# Control.net
KiCad netlist of a schematic drawn in Altium Designer
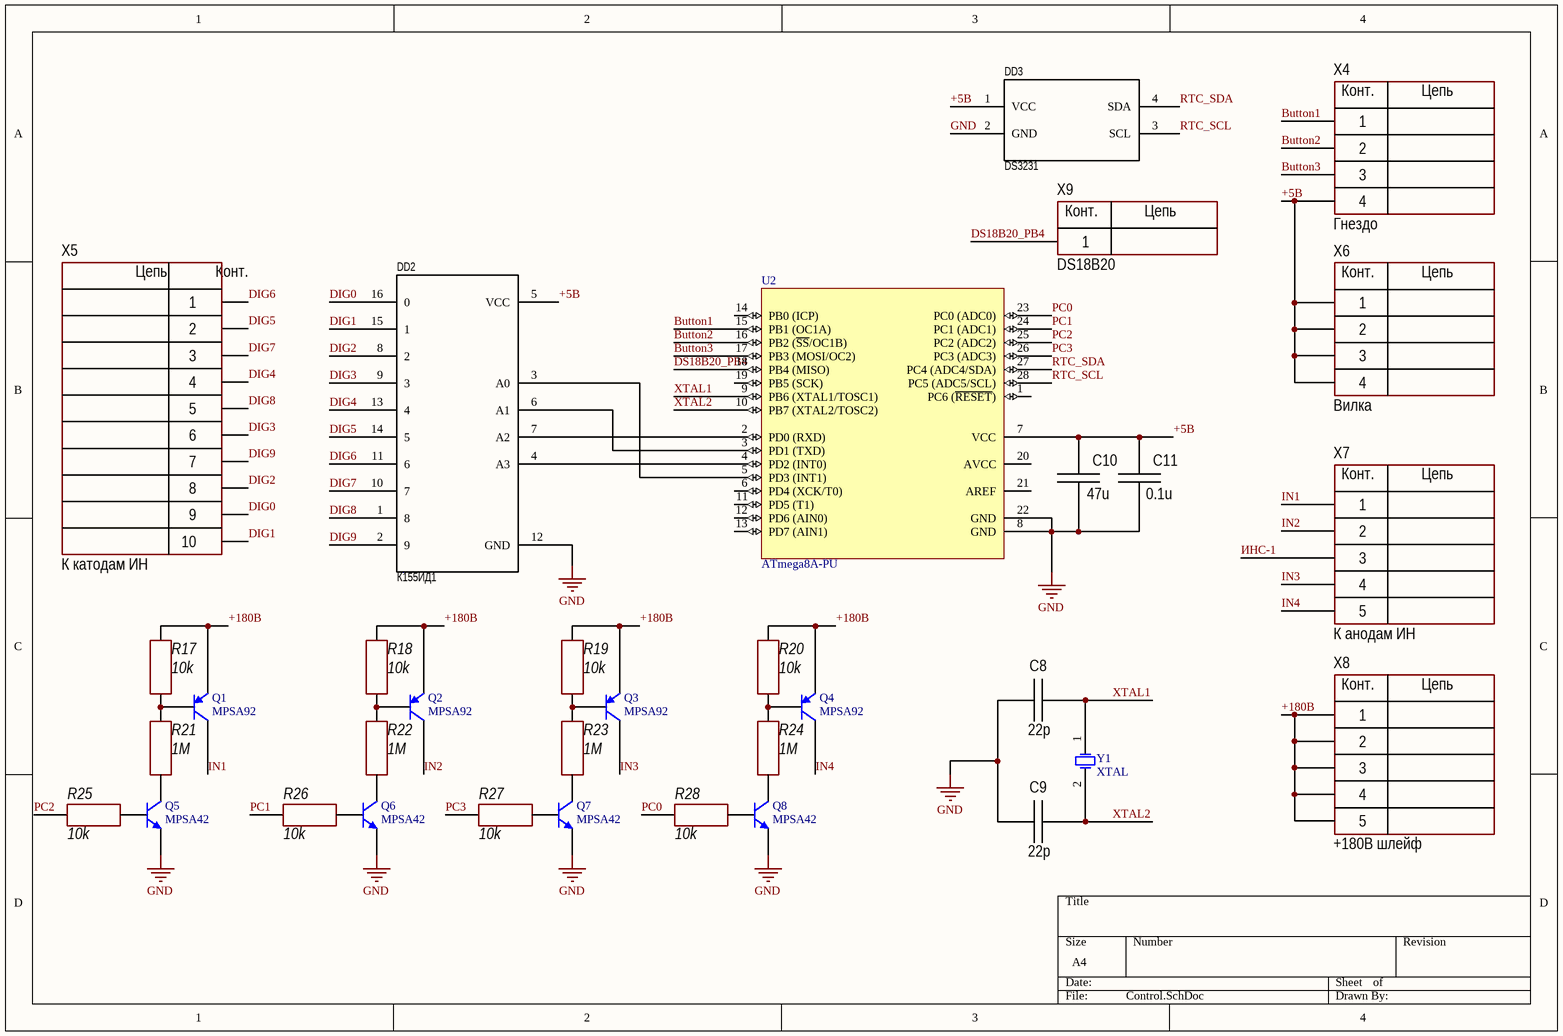
[diagram p0: Control.SchDoc]

(export (version "E")
  (design (tool "Eeschema 10.0.6"))
  (components
    (comp (ref "C8") (value "22p") (footprint "CAP: DEBB33D") (libsource (lib "Discrete") (part "Capacitor")))
    (comp (ref "C9") (value "22p") (footprint "CAP: DEBB33D") (libsource (lib "Discrete") (part "Capacitor")))
    (comp (ref "C10")
      (value "47u")
      (footprint "CAP: DEBB33D")
      (libsource (lib "Discrete") (part "Capacitor"))
    )
    (comp (ref "C11")
      (value "0.1u")
      (footprint "CAP: DEBB33D")
      (libsource (lib "Discrete") (part "Capacitor"))
    )
    (comp (ref "DD2") (value "К155ИД1") (footprint "DIP16") (libsource (lib "K155ID1") (part "K155ID1")))
    (comp (ref "DD3") (value "DS3231") (footprint "DS3231") (libsource (lib "DS3231") (part "DS3231")))
    (comp (ref "Q1")
      (value "MPSA92")
      (footprint "TO-92A")
      (description "PNP General Purpose Amplifier")
      (fields (field (name "PUBLISHER") "Altium Limited"))
      (libsource (lib "Miscellaneous Devices") (part "2N3906"))
    )
    (comp (ref "Q2")
      (value "MPSA92")
      (footprint "TO-92A")
      (description "PNP General Purpose Amplifier")
      (fields (field (name "PUBLISHER") "Altium Limited"))
      (libsource (lib "Miscellaneous Devices") (part "2N3906"))
    )
    (comp (ref "Q3")
      (value "MPSA92")
      (footprint "TO-92A")
      (description "PNP General Purpose Amplifier")
      (fields (field (name "PUBLISHER") "Altium Limited"))
      (libsource (lib "Miscellaneous Devices") (part "2N3906"))
    )
    (comp (ref "Q4")
      (value "MPSA92")
      (footprint "TO-92A")
      (description "PNP General Purpose Amplifier")
      (fields (field (name "PUBLISHER") "Altium Limited"))
      (libsource (lib "Miscellaneous Devices") (part "2N3906"))
    )
    (comp (ref "Q5")
      (value "MPSA42")
      (footprint "TO-92A")
      (description "NPN General Purpose Amplifier")
      (fields (field (name "PUBLISHER") "Altium Limited"))
      (libsource (lib "Miscellaneous Devices") (part "2N3904"))
    )
    (comp (ref "Q6")
      (value "MPSA42")
      (footprint "TO-92A")
      (description "NPN General Purpose Amplifier")
      (fields (field (name "PUBLISHER") "Altium Limited"))
      (libsource (lib "Miscellaneous Devices") (part "2N3904"))
    )
    (comp (ref "Q7")
      (value "MPSA42")
      (footprint "TO-92A")
      (description "NPN General Purpose Amplifier")
      (fields (field (name "PUBLISHER") "Altium Limited"))
      (libsource (lib "Miscellaneous Devices") (part "2N3904"))
    )
    (comp (ref "Q8")
      (value "MPSA42")
      (footprint "TO-92A")
      (description "NPN General Purpose Amplifier")
      (fields (field (name "PUBLISHER") "Altium Limited"))
      (libsource (lib "Miscellaneous Devices") (part "2N3904"))
    )
    (comp (ref "R17")
      (value "10k")
      (footprint "MLT")
      (description "MLT")
      (libsource (lib "") (part "Resistor_1"))
    )
    (comp (ref "R18")
      (value "10k")
      (footprint "MLT")
      (description "MLT")
      (libsource (lib "") (part "Resistor_1"))
    )
    (comp (ref "R19")
      (value "10k")
      (footprint "MLT")
      (description "MLT")
      (libsource (lib "") (part "Resistor_1"))
    )
    (comp (ref "R20")
      (value "10k")
      (footprint "MLT")
      (description "MLT")
      (libsource (lib "") (part "Resistor_1"))
    )
    (comp (ref "R21")
      (value "1M")
      (footprint "MLT")
      (description "MLT")
      (libsource (lib "") (part "Resistor_1"))
    )
    (comp (ref "R22")
      (value "1M")
      (footprint "MLT")
      (description "MLT")
      (libsource (lib "") (part "Resistor_1"))
    )
    (comp (ref "R23")
      (value "1M")
      (footprint "MLT")
      (description "MLT")
      (libsource (lib "") (part "Resistor_1"))
    )
    (comp (ref "R24")
      (value "1M")
      (footprint "MLT")
      (description "MLT")
      (libsource (lib "") (part "Resistor_1"))
    )
    (comp (ref "R25")
      (value "10k")
      (footprint "MLT")
      (description "MLT")
      (libsource (lib "Resistor_MLT") (part "Resistor"))
    )
    (comp (ref "R26")
      (value "10k")
      (footprint "MLT")
      (description "MLT")
      (libsource (lib "Resistor_MLT") (part "Resistor"))
    )
    (comp (ref "R27")
      (value "10k")
      (footprint "MLT")
      (description "MLT")
      (libsource (lib "Resistor_MLT") (part "Resistor"))
    )
    (comp (ref "R28")
      (value "10k")
      (footprint "MLT")
      (description "MLT")
      (libsource (lib "Resistor_MLT") (part "Resistor"))
    )
    (comp (ref "U2")
      (value "ATmega8A-PU")
      (footprint "28P3")
      (fields (field (name "PUBLISHER") "Altium Limited"))
      (libsource (lib "Atmel Microcontroller 8-Bit megaAVR") (part "ATmega8A-PU"))
    )
    (comp (ref "X4")
      (value "Гнездо")
      (footprint "CON: PBS-4")
      (libsource (lib "Connectors") (part "4-Connector"))
    )
    (comp (ref "X5")
      (value "К катодам ИН")
      (footprint "CON: PBS-10")
      (libsource (lib "Connectors") (part "10-Connector"))
    )
    (comp (ref "X6")
      (value "Вилка")
      (footprint "CON: PLS-4")
      (libsource (lib "Connectors") (part "4-Connector"))
    )
    (comp (ref "X7")
      (value "К анодам ИН")
      (footprint "CON: PBS-5")
      (libsource (lib "Connectors") (part "5-Connector"))
    )
    (comp (ref "X8")
      (value "+180В шлейф")
      (footprint "CON: PBS-5")
      (libsource (lib "Connectors") (part "5-Connector"))
    )
    (comp (ref "X9")
      (value "DS18B20")
      (footprint "CON: PADS 1x1mm")
      (libsource (lib "Connectors") (part "1-Connector"))
    )
    (comp (ref "Y1")
      (value "XTAL")
      (footprint "R38")
      (description "Crystal Oscillator")
      (fields (field (name "PUBLISHER") "Altium Limited"))
      (libsource (lib "Miscellaneous Devices") (part "XTAL"))
    )
  )
  (nets
    (net (code "1") (name "/+5В") (class "Default")
      (node (ref "C10") (pin "1") (pinfunction "1_1") (pintype "power_in"))
      (node (ref "C11") (pin "1") (pinfunction "1_1") (pintype "power_in"))
      (node (ref "DD2") (pin "5") (pinfunction "VCC_5") (pintype "passive"))
      (node (ref "DD3") (pin "1") (pinfunction "VCC_1") (pintype "passive"))
      (node (ref "U2") (pin "7") (pinfunction "VCC_7") (pintype "power_in"))
      (node (ref "X4") (pin "4") (pinfunction "4_4") (pintype "power_in"))
      (node (ref "X6") (pin "1") (pinfunction "1_1") (pintype "passive"))
      (node (ref "X6") (pin "2") (pinfunction "2_2") (pintype "passive"))
      (node (ref "X6") (pin "3") (pinfunction "3_3") (pintype "power_in"))
      (node (ref "X6") (pin "4") (pinfunction "4_4") (pintype "power_in"))
    )
    (net (code "2") (name "/+180В") (class "Default")
      (node (ref "Q1") (pin "1") (pinfunction "E_1") (pintype "passive"))
      (node (ref "Q2") (pin "1") (pinfunction "E_1") (pintype "passive"))
      (node (ref "Q3") (pin "1") (pinfunction "E_1") (pintype "passive"))
      (node (ref "Q4") (pin "1") (pinfunction "E_1") (pintype "passive"))
      (node (ref "R17") (pin "2") (pintype "passive"))
      (node (ref "R18") (pin "2") (pintype "passive"))
      (node (ref "R19") (pin "2") (pintype "passive"))
      (node (ref "R20") (pin "2") (pintype "passive"))
      (node (ref "X8") (pin "1") (pinfunction "1_1") (pintype "passive"))
      (node (ref "X8") (pin "2") (pinfunction "2_2") (pintype "passive"))
      (node (ref "X8") (pin "3") (pinfunction "3_3") (pintype "power_in"))
      (node (ref "X8") (pin "4") (pinfunction "4_4") (pintype "power_in"))
      (node (ref "X8") (pin "5") (pinfunction "5_5") (pintype "power_in"))
    )
    (net (code "3") (name "/Button1") (class "Default")
      (node (ref "U2") (pin "15") (pinfunction "PB1_(OC1A)_15") (pintype "bidirectional"))
      (node (ref "X4") (pin "1") (pinfunction "1_1") (pintype "passive"))
    )
    (net (code "4") (name "/Button2") (class "Default")
      (node (ref "U2") (pin "16") (pinfunction "PB2_(~{SS}/OC1B)_16") (pintype "bidirectional"))
      (node (ref "X4") (pin "2") (pinfunction "2_2") (pintype "passive"))
    )
    (net (code "5") (name "/Button3") (class "Default")
      (node (ref "U2") (pin "17") (pinfunction "PB3_(MOSI/OC2)_17") (pintype "bidirectional"))
      (node (ref "X4") (pin "3") (pinfunction "3_3") (pintype "power_in"))
    )
    (net (code "6") (name "/DIG0") (class "Default")
      (node (ref "DD2") (pin "16") (pinfunction "0_16") (pintype "passive"))
      (node (ref "X5") (pin "9") (pinfunction "9_9") (pintype "power_in"))
    )
    (net (code "7") (name "/DIG1") (class "Default")
      (node (ref "DD2") (pin "15") (pinfunction "1_15") (pintype "passive"))
      (node (ref "X5") (pin "10") (pinfunction "10_10") (pintype "power_in"))
    )
    (net (code "8") (name "/DIG2") (class "Default")
      (node (ref "DD2") (pin "8") (pinfunction "2_8") (pintype "passive"))
      (node (ref "X5") (pin "8") (pinfunction "8_8") (pintype "power_in"))
    )
    (net (code "9") (name "/DIG3") (class "Default")
      (node (ref "DD2") (pin "9") (pinfunction "3_9") (pintype "passive"))
      (node (ref "X5") (pin "6") (pinfunction "6_6") (pintype "power_in"))
    )
    (net (code "10") (name "/DIG4") (class "Default")
      (node (ref "DD2") (pin "13") (pinfunction "4_13") (pintype "passive"))
      (node (ref "X5") (pin "4") (pinfunction "4_4") (pintype "power_in"))
    )
    (net (code "11") (name "/DIG5") (class "Default")
      (node (ref "DD2") (pin "14") (pinfunction "5_14") (pintype "passive"))
      (node (ref "X5") (pin "2") (pinfunction "2_2") (pintype "passive"))
    )
    (net (code "12") (name "/DIG6") (class "Default")
      (node (ref "DD2") (pin "11") (pinfunction "6_11") (pintype "passive"))
      (node (ref "X5") (pin "1") (pinfunction "1_1") (pintype "passive"))
    )
    (net (code "13") (name "/DIG7") (class "Default")
      (node (ref "DD2") (pin "10") (pinfunction "7_10") (pintype "passive"))
      (node (ref "X5") (pin "3") (pinfunction "3_3") (pintype "power_in"))
    )
    (net (code "14") (name "/DIG8") (class "Default")
      (node (ref "DD2") (pin "1") (pinfunction "8_1") (pintype "passive"))
      (node (ref "X5") (pin "5") (pinfunction "5_5") (pintype "power_in"))
    )
    (net (code "15") (name "/DIG9") (class "Default")
      (node (ref "DD2") (pin "2") (pinfunction "9_2") (pintype "passive"))
      (node (ref "X5") (pin "7") (pinfunction "7_7") (pintype "power_in"))
    )
    (net (code "16") (name "/DS18B20_PB4") (class "Default")
      (node (ref "U2") (pin "18") (pinfunction "PB4_(MISO)_18") (pintype "bidirectional"))
      (node (ref "X9") (pin "1") (pinfunction "1_1") (pintype "passive"))
    )
    (net (code "17") (name "/IN1") (class "Default")
      (node (ref "Q1") (pin "3") (pinfunction "C_3") (pintype "passive"))
      (node (ref "X7") (pin "1") (pinfunction "1_1") (pintype "passive"))
    )
    (net (code "18") (name "/IN2") (class "Default")
      (node (ref "Q2") (pin "3") (pinfunction "C_3") (pintype "passive"))
      (node (ref "X7") (pin "2") (pinfunction "2_2") (pintype "passive"))
    )
    (net (code "19") (name "/IN3") (class "Default")
      (node (ref "Q3") (pin "3") (pinfunction "C_3") (pintype "passive"))
      (node (ref "X7") (pin "4") (pinfunction "4_4") (pintype "power_in"))
    )
    (net (code "20") (name "/IN4") (class "Default")
      (node (ref "Q4") (pin "3") (pinfunction "C_3") (pintype "passive"))
      (node (ref "X7") (pin "5") (pinfunction "5_5") (pintype "power_in"))
    )
    (net (code "21") (name "/PC0") (class "Default")
      (node (ref "R28") (pin "2") (pintype "passive"))
      (node (ref "U2") (pin "23") (pinfunction "PC0_(ADC0)_23") (pintype "bidirectional"))
    )
    (net (code "22") (name "/PC1") (class "Default")
      (node (ref "R26") (pin "2") (pintype "passive"))
      (node (ref "U2") (pin "24") (pinfunction "PC1_(ADC1)_24") (pintype "bidirectional"))
    )
    (net (code "23") (name "/PC2") (class "Default")
      (node (ref "R25") (pin "2") (pintype "passive"))
      (node (ref "U2") (pin "25") (pinfunction "PC2_(ADC2)_25") (pintype "bidirectional"))
    )
    (net (code "24") (name "/PC3") (class "Default")
      (node (ref "R27") (pin "2") (pintype "passive"))
      (node (ref "U2") (pin "26") (pinfunction "PC3_(ADC3)_26") (pintype "bidirectional"))
    )
    (net (code "25") (name "/RTC_SCL") (class "Default")
      (node (ref "DD3") (pin "3") (pinfunction "SCL_3") (pintype "passive"))
      (node (ref "U2") (pin "28") (pinfunction "PC5_(ADC5/SCL)_28") (pintype "bidirectional"))
    )
    (net (code "26") (name "/RTC_SDA") (class "Default")
      (node (ref "DD3") (pin "4") (pinfunction "SDA_4") (pintype "passive"))
      (node (ref "U2") (pin "27") (pinfunction "PC4_(ADC4/SDA)_27") (pintype "bidirectional"))
    )
    (net (code "27") (name "/XTAL1") (class "Default")
      (node (ref "C8") (pin "2") (pinfunction "2_2") (pintype "power_in"))
      (node (ref "U2") (pin "9") (pinfunction "PB6_(XTAL1/TOSC1)_9") (pintype "bidirectional"))
      (node (ref "Y1") (pin "1") (pinfunction "OSC1_1") (pintype "passive"))
    )
    (net (code "28") (name "/XTAL2") (class "Default")
      (node (ref "C9") (pin "2") (pinfunction "2_2") (pintype "power_in"))
      (node (ref "U2") (pin "10") (pinfunction "PB7_(XTAL2/TOSC2)_10") (pintype "bidirectional"))
      (node (ref "Y1") (pin "2") (pinfunction "OSC2_2") (pintype "passive"))
    )
    (net (code "29") (name "/ИНС-1") (class "Default")
      (node (ref "X7") (pin "3") (pinfunction "3_3") (pintype "power_in"))
    )
    (net (code "30") (name "GND") (class "Default")
      (node (ref "C10") (pin "2") (pinfunction "2_2") (pintype "power_in"))
      (node (ref "C11") (pin "2") (pinfunction "2_2") (pintype "power_in"))
      (node (ref "C8") (pin "1") (pinfunction "1_1") (pintype "power_in"))
      (node (ref "C9") (pin "1") (pinfunction "1_1") (pintype "power_in"))
      (node (ref "DD2") (pin "12") (pinfunction "GND_12") (pintype "passive"))
      (node (ref "DD3") (pin "2") (pinfunction "GND_2") (pintype "passive"))
      (node (ref "Q5") (pin "1") (pinfunction "E_1") (pintype "passive"))
      (node (ref "Q6") (pin "1") (pinfunction "E_1") (pintype "passive"))
      (node (ref "Q7") (pin "1") (pinfunction "E_1") (pintype "passive"))
      (node (ref "Q8") (pin "1") (pinfunction "E_1") (pintype "passive"))
      (node (ref "U2") (pin "22") (pinfunction "GND_22") (pintype "power_in"))
      (node (ref "U2") (pin "8") (pinfunction "GND_8") (pintype "power_in"))
    )
    (net (code "31") (name "Net-(DD2-A0)") (class "Default")
      (node (ref "DD2") (pin "3") (pinfunction "A0_3") (pintype "passive"))
      (node (ref "U2") (pin "5") (pinfunction "PD3_(INT1)_5") (pintype "bidirectional"))
    )
    (net (code "32") (name "Net-(DD2-A1)") (class "Default")
      (node (ref "DD2") (pin "6") (pinfunction "A1_6") (pintype "passive"))
      (node (ref "U2") (pin "3") (pinfunction "PD1_(TXD)_3") (pintype "bidirectional"))
    )
    (net (code "33") (name "Net-(DD2-A2)") (class "Default")
      (node (ref "DD2") (pin "7") (pinfunction "A2_7") (pintype "passive"))
      (node (ref "U2") (pin "2") (pinfunction "PD0_(RXD)_2") (pintype "bidirectional"))
    )
    (net (code "34") (name "Net-(DD2-A3)") (class "Default")
      (node (ref "DD2") (pin "4") (pinfunction "A3_4") (pintype "passive"))
      (node (ref "U2") (pin "4") (pinfunction "PD2_(INT0)_4") (pintype "bidirectional"))
    )
    (net (code "35") (name "Net-(Q1-B)") (class "Default")
      (node (ref "Q1") (pin "2") (pinfunction "B_2") (pintype "passive"))
      (node (ref "R17") (pin "1") (pintype "passive"))
      (node (ref "R21") (pin "2") (pintype "passive"))
    )
    (net (code "36") (name "Net-(Q2-B)") (class "Default")
      (node (ref "Q2") (pin "2") (pinfunction "B_2") (pintype "passive"))
      (node (ref "R18") (pin "1") (pintype "passive"))
      (node (ref "R22") (pin "2") (pintype "passive"))
    )
    (net (code "37") (name "Net-(Q3-B)") (class "Default")
      (node (ref "Q3") (pin "2") (pinfunction "B_2") (pintype "passive"))
      (node (ref "R19") (pin "1") (pintype "passive"))
      (node (ref "R23") (pin "2") (pintype "passive"))
    )
    (net (code "38") (name "Net-(Q4-B)") (class "Default")
      (node (ref "Q4") (pin "2") (pinfunction "B_2") (pintype "passive"))
      (node (ref "R20") (pin "1") (pintype "passive"))
      (node (ref "R24") (pin "2") (pintype "passive"))
    )
    (net (code "39") (name "Net-(Q5-B)") (class "Default")
      (node (ref "Q5") (pin "2") (pinfunction "B_2") (pintype "passive"))
      (node (ref "R25") (pin "1") (pintype "passive"))
    )
    (net (code "40") (name "Net-(Q5-C)") (class "Default")
      (node (ref "Q5") (pin "3") (pinfunction "C_3") (pintype "passive"))
      (node (ref "R21") (pin "1") (pintype "passive"))
    )
    (net (code "41") (name "Net-(Q6-B)") (class "Default")
      (node (ref "Q6") (pin "2") (pinfunction "B_2") (pintype "passive"))
      (node (ref "R26") (pin "1") (pintype "passive"))
    )
    (net (code "42") (name "Net-(Q6-C)") (class "Default")
      (node (ref "Q6") (pin "3") (pinfunction "C_3") (pintype "passive"))
      (node (ref "R22") (pin "1") (pintype "passive"))
    )
    (net (code "43") (name "Net-(Q7-B)") (class "Default")
      (node (ref "Q7") (pin "2") (pinfunction "B_2") (pintype "passive"))
      (node (ref "R27") (pin "1") (pintype "passive"))
    )
    (net (code "44") (name "Net-(Q7-C)") (class "Default")
      (node (ref "Q7") (pin "3") (pinfunction "C_3") (pintype "passive"))
      (node (ref "R23") (pin "1") (pintype "passive"))
    )
    (net (code "45") (name "Net-(Q8-B)") (class "Default")
      (node (ref "Q8") (pin "2") (pinfunction "B_2") (pintype "passive"))
      (node (ref "R28") (pin "1") (pintype "passive"))
    )
    (net (code "46") (name "Net-(Q8-C)") (class "Default")
      (node (ref "Q8") (pin "3") (pinfunction "C_3") (pintype "passive"))
      (node (ref "R24") (pin "1") (pintype "passive"))
    )
    (net (code "47") (name "unconnected-(U2-AREF-Pad21)") (class "Default")
      (node (ref "U2") (pin "21") (pinfunction "AREF_21") (pintype "passive"))
    )
    (net (code "48") (name "unconnected-(U2-AVCC-Pad20)") (class "Default")
      (node (ref "U2") (pin "20") (pinfunction "AVCC_20") (pintype "power_in"))
    )
    (net (code "49") (name "unconnected-(U2-PB0_(ICP)-Pad14)") (class "Default")
      (node (ref "U2") (pin "14") (pinfunction "PB0_(ICP)_14") (pintype "bidirectional"))
    )
    (net (code "50") (name "unconnected-(U2-PB5_(SCK)-Pad19)") (class "Default")
      (node (ref "U2") (pin "19") (pinfunction "PB5_(SCK)_19") (pintype "bidirectional"))
    )
    (net (code "51") (name "unconnected-(U2-PC6_(~{RESET})-Pad1)") (class "Default")
      (node (ref "U2") (pin "1") (pinfunction "PC6_(~{RESET})_1") (pintype "bidirectional"))
    )
    (net (code "52") (name "unconnected-(U2-PD4_(XCK{slash}T0)-Pad6)") (class "Default")
      (node (ref "U2") (pin "6") (pinfunction "PD4_(XCK/T0)_6") (pintype "bidirectional"))
    )
    (net (code "53") (name "unconnected-(U2-PD5_(T1)-Pad11)") (class "Default")
      (node (ref "U2") (pin "11") (pinfunction "PD5_(T1)_11") (pintype "bidirectional"))
    )
    (net (code "54") (name "unconnected-(U2-PD6_(AIN0)-Pad12)") (class "Default")
      (node (ref "U2") (pin "12") (pinfunction "PD6_(AIN0)_12") (pintype "bidirectional"))
    )
    (net (code "55") (name "unconnected-(U2-PD7_(AIN1)-Pad13)") (class "Default")
      (node (ref "U2") (pin "13") (pinfunction "PD7_(AIN1)_13") (pintype "bidirectional"))
    )
  )
)
